# Connectivity.net
KiCad netlist of a schematic drawn in Altium Designer
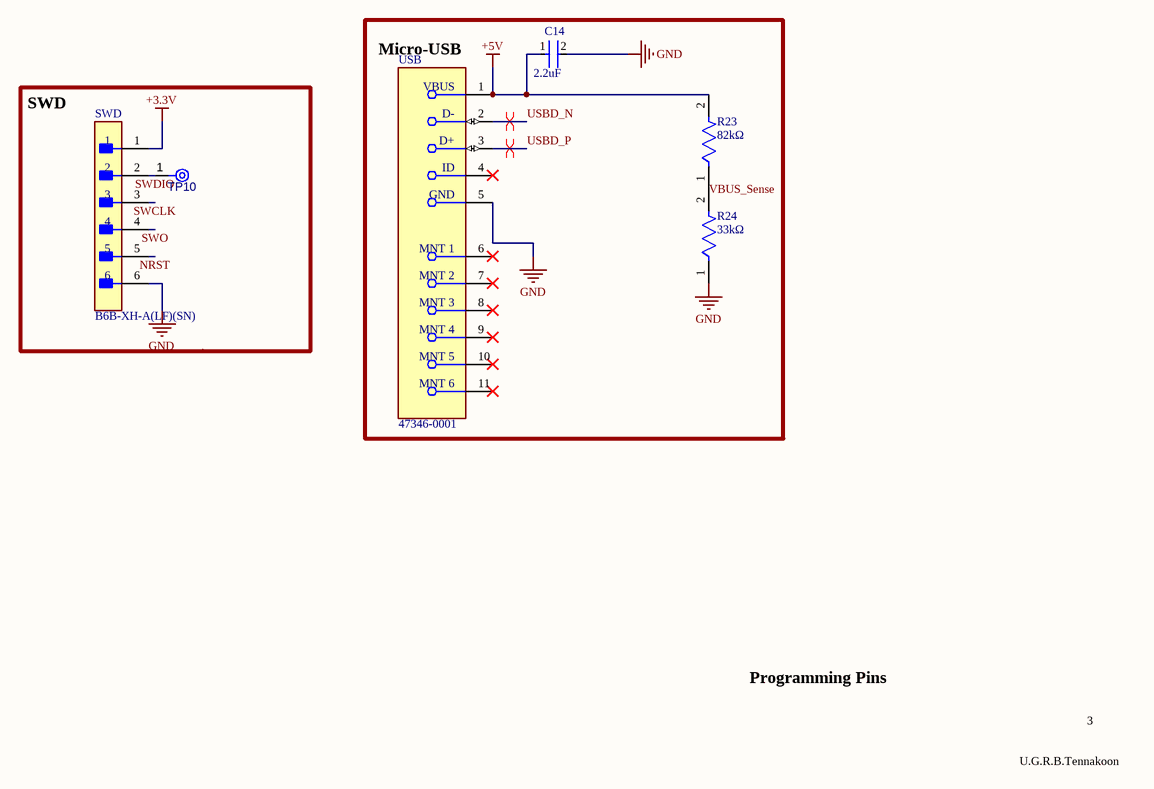
[diagram p0: Connectivity.SchDoc]

(export (version "E")
  (design (tool "Eeschema 10.0.6"))
  (components
    (comp (ref "C14")
      (value "2.2uF")
      (footprint "FP-C1210C225K1RACAUTO-MFG")
      (description "C1210C225K1RACAUTOCAP CER 2.2UF 100V X7R 1210")
      (fields (field (name "TOLERANCE") "10%"))
      (libsource (lib "Altium Content Vault") (part "b4654b650e69147ec39a6b967a45e02"))
    )
    (comp (ref "R23")
      (value "82kΩ")
      (footprint "FP-SR0805-MFG")
      (description "0805W8F8202T5E")
      (fields (field (name "MANUFACTURER PART NUMBER") "SR0805FR-4710KL") (field (name "TOLERANCE") "0.01"))
      (libsource (lib "Altium Content Vault") (part "1029c3af85768c4190bb7ad29bc67b5"))
    )
    (comp (ref "R24")
      (value "33kΩ")
      (footprint "FP-SR0805-MFG")
      (description "0805W8F3302T5E")
      (fields (field (name "MANUFACTURER PART NUMBER") "SR0805FR-4710KL") (field (name "TOLERANCE") "0.01"))
      (libsource (lib "Altium Content Vault") (part "1029c3af85768c4190bb7ad29bc67b5"))
    )
    (comp (ref "SWD")
      (value "B6B-XH-A(LF)(SN)")
      (footprint "FP-B6B-XH-A_LF_SN-MFG")
      (description "CONN HEADER VERT 6POS 2.5MM")
      (libsource (lib "Altium Content Vault") (part "f2cb566baf1c37ab5a3b8e90bbeafd6"))
    )
    (comp (ref "TP10")
      (value "TPAD6R")
      (footprint "TP06R")
      (description "0.6mm round")
      (libsource (lib "ravindu tennakoon") (part "CMP-001-0001-4"))
    )
    (comp (ref "USB")
      (value "47346-0001")
      (footprint "FP-473460001-MFG")
      (description "Micro-USB B Receptacle with Flange, Bottom Mount, Surface Mount, Lead-Free")
      (libsource (lib "ravindu tennakoon") (part "53ae1f1d9b557310b43ca686e5bb76a"))
    )
  )
  (nets
    (net (code "1") (name "+3.3V") (class "Default")
      (node (ref "SWD") (pin "1") (pinfunction "1_1") (pintype "passive"))
    )
    (net (code "2") (name "+5V") (class "Default")
      (node (ref "C14") (pin "1") (pinfunction "1_1") (pintype "passive"))
      (node (ref "R23") (pin "2") (pinfunction "2_2") (pintype "passive"))
      (node (ref "USB") (pin "1") (pinfunction "VBUS_1") (pintype "power_in"))
    )
    (net (code "3") (name "/NRST") (class "Default")
      (node (ref "SWD") (pin "5") (pinfunction "5_5") (pintype "passive"))
    )
    (net (code "4") (name "/SWCLK") (class "Default")
      (node (ref "SWD") (pin "3") (pinfunction "3_3") (pintype "passive"))
    )
    (net (code "5") (name "/SWDIO") (class "Default")
      (node (ref "SWD") (pin "2") (pinfunction "2_2") (pintype "passive"))
      (node (ref "TP10") (pin "1") (pinfunction "TP_1") (pintype "passive"))
    )
    (net (code "6") (name "/SWO") (class "Default")
      (node (ref "SWD") (pin "4") (pinfunction "4_4") (pintype "passive"))
    )
    (net (code "7") (name "/USBD_N") (class "Default")
      (node (ref "USB") (pin "2") (pinfunction "D-_2") (pintype "bidirectional"))
    )
    (net (code "8") (name "/USBD_P") (class "Default")
      (node (ref "USB") (pin "3") (pinfunction "D+_3") (pintype "bidirectional"))
    )
    (net (code "9") (name "/VBUS_Sense") (class "Default")
      (node (ref "R23") (pin "1") (pinfunction "1_1") (pintype "passive"))
      (node (ref "R24") (pin "2") (pinfunction "2_2") (pintype "passive"))
    )
    (net (code "10") (name "GND") (class "Default")
      (node (ref "C14") (pin "2") (pinfunction "2_2") (pintype "passive"))
      (node (ref "R24") (pin "1") (pinfunction "1_1") (pintype "passive"))
      (node (ref "SWD") (pin "6") (pinfunction "6_6") (pintype "passive"))
      (node (ref "USB") (pin "5") (pinfunction "GND_5") (pintype "power_in"))
    )
    (net (code "11") (name "unconnected-(USB-ID-Pad4)") (class "Default")
      (node (ref "USB") (pin "4") (pinfunction "ID_4") (pintype "passive+no_connect"))
    )
    (net (code "12") (name "unconnected-(USB-MNT_1-Pad6)") (class "Default")
      (node (ref "USB") (pin "6") (pinfunction "MNT_1_6") (pintype "passive+no_connect"))
    )
    (net (code "13") (name "unconnected-(USB-MNT_2-Pad7)") (class "Default")
      (node (ref "USB") (pin "7") (pinfunction "MNT_2_7") (pintype "passive+no_connect"))
    )
    (net (code "14") (name "unconnected-(USB-MNT_3-Pad8)") (class "Default")
      (node (ref "USB") (pin "8") (pinfunction "MNT_3_8") (pintype "passive+no_connect"))
    )
    (net (code "15") (name "unconnected-(USB-MNT_4-Pad9)") (class "Default")
      (node (ref "USB") (pin "9") (pinfunction "MNT_4_9") (pintype "passive+no_connect"))
    )
    (net (code "16") (name "unconnected-(USB-MNT_5-Pad10)") (class "Default")
      (node (ref "USB") (pin "10") (pinfunction "MNT_5_10") (pintype "passive+no_connect"))
    )
    (net (code "17") (name "unconnected-(USB-MNT_6-Pad11)") (class "Default")
      (node (ref "USB") (pin "11") (pinfunction "MNT_6_11") (pintype "passive+no_connect"))
    )
  )
)
